# AUX_power_board_V3_4.net
KiCad netlist of a schematic drawn in EAGLE
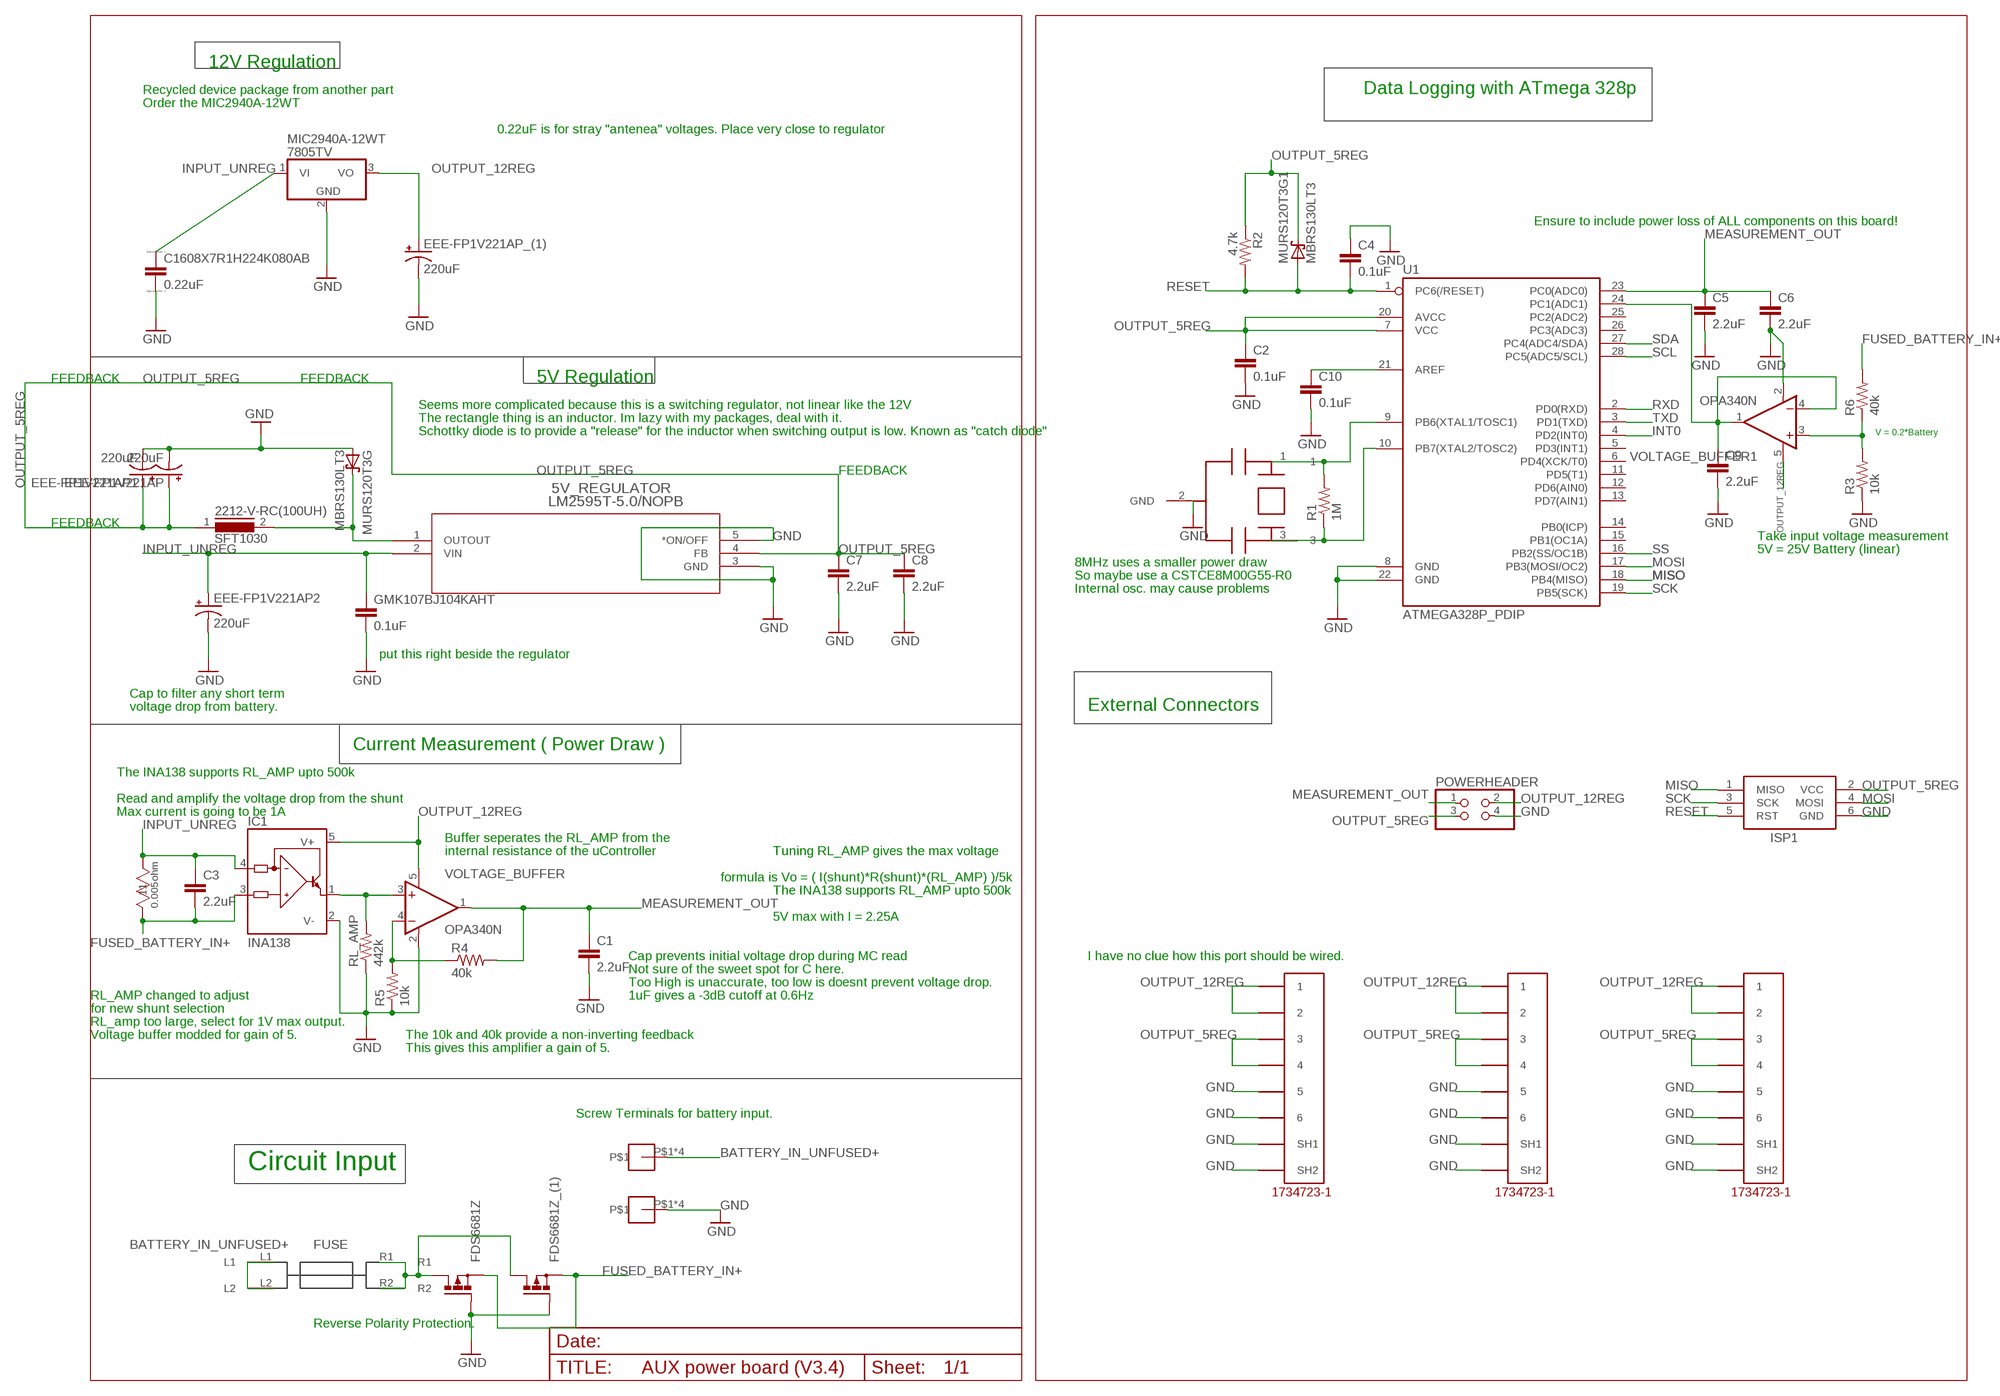
[diagram p0: schematic, sheet 1]

(export (version "E")
  (design (tool "Eeschema 10.0.6"))
  (components
    (comp (ref "5V_REGULATOR")
      (value "LM2595T-5.0/NOPB")
      (footprint "eagle-import:T05D")
      (fields
        (field (name "MANUFACTURER_PART_NUMBER") "LM2595T50")
        (field (name "COPYRIGHT") "Copyright C 2015 Accelerated Designs. All rights reserved")
      )
      (libsource (lib "eagle-import") (part "LM2595T-5.0/NOPB"))
    )
    (comp (ref "15FR005E")
      (value "15FR005E")
      (footprint "eagle-import:RES_15")
      (fields (field (name "COPYRIGHT") "Copyright C 2015 Accelerated Designs. All rights reserved"))
      (libsource (lib "eagle-import") (part "15FR005E"))
    )
    (comp (ref "2212-V-RC(100UH)")
      (value "SFT1030")
      (footprint "eagle-import:SFT1030")
      (libsource (lib "eagle-import") (part "SFT1030"))
    )
    (comp (ref "C1")
      (value "2.2uF")
      (footprint "eagle-import:C0603")
      (libsource (lib "eagle-import") (part "resistor_C-EUC0603"))
    )
    (comp (ref "C2")
      (value "0.1uF")
      (footprint "eagle-import:C0603")
      (libsource (lib "eagle-import") (part "resistor_C-EUC0603"))
    )
    (comp (ref "C3")
      (value "2.2uF")
      (footprint "eagle-import:C0603")
      (libsource (lib "eagle-import") (part "C-EUC0603"))
    )
    (comp (ref "C4")
      (value "0.1uF")
      (footprint "eagle-import:C0603")
      (libsource (lib "eagle-import") (part "C-EUC0603"))
    )
    (comp (ref "C5")
      (value "2.2uF")
      (footprint "eagle-import:C0603")
      (libsource (lib "eagle-import") (part "C-EUC0603"))
    )
    (comp (ref "C6")
      (value "2.2uF")
      (footprint "eagle-import:C0603")
      (libsource (lib "eagle-import") (part "C-EUC0603"))
    )
    (comp (ref "C7")
      (value "2.2uF")
      (footprint "eagle-import:C0603")
      (libsource (lib "eagle-import") (part "C-EUC0603"))
    )
    (comp (ref "C8")
      (value "2.2uF")
      (footprint "eagle-import:C0603")
      (libsource (lib "eagle-import") (part "C-EUC0603"))
    )
    (comp (ref "C9")
      (value "2.2uF")
      (footprint "eagle-import:C0603")
      (libsource (lib "eagle-import") (part "C-EUC0603"))
    )
    (comp (ref "C10")
      (value "0.1uF")
      (footprint "eagle-import:C0603")
      (libsource (lib "eagle-import") (part "resistor_C-EUC0603"))
    )
    (comp (ref "C1608X7R1H224K080AB")
      (value "0.22uF")
      (footprint "eagle-import:C0603")
      (libsource (lib "eagle-import") (part "CC0603"))
    )
    (comp (ref "CSTCE8M00G55-R0")
      (value "CSTCE16M0V53-R0")
      (footprint "eagle-import:RESONATOR")
      (libsource (lib "eagle-import") (part "CSTCE16M0V53-R0"))
    )
    (comp (ref "EEE-FP1V221AP")
      (value "220uF")
      (footprint "eagle-import:175TMP-0808")
      (libsource (lib "eagle-import") (part "CPOL-US175TMP-0808"))
    )
    (comp (ref "EEE-FP1V221AP1")
      (value "220uF")
      (footprint "eagle-import:175TMP-0808")
      (libsource (lib "eagle-import") (part "CPOL-US175TMP-0808"))
    )
    (comp (ref "EEE-FP1V221AP2")
      (value "220uF")
      (footprint "eagle-import:175TMP-0808")
      (libsource (lib "eagle-import") (part "CPOL-US175TMP-0808"))
    )
    (comp (ref "EEE-FP1V221AP_(1)")
      (value "220uF")
      (footprint "eagle-import:175TMP-0808")
      (libsource (lib "eagle-import") (part "CPOL-US175TMP-0808"))
    )
    (comp (ref "FDS6681Z")
      (value "P-MOSFET-SO8")
      (footprint "eagle-import:SO-08")
      (libsource (lib "eagle-import") (part "P-MOSFET-SO8"))
    )
    (comp (ref "FDS6681Z_(1)")
      (value "P-MOSFET-SO8")
      (footprint "eagle-import:SO-08")
      (libsource (lib "eagle-import") (part "P-MOSFET-SO8"))
    )
    (comp (ref "GMK107BJ104KAHT")
      (value "0.1uF")
      (footprint "eagle-import:C0603")
      (libsource (lib "eagle-import") (part "C-EUC0603"))
    )
    (comp (ref "IC1")
      (value "INA138")
      (footprint "eagle-import:SOT23-5")
      (fields (field (name "MF") "TEXAS INSTRUMENTS") (field (name "MPN") "INA138NA/250"))
      (libsource (lib "eagle-import") (part "INA138"))
    )
    (comp (ref "ISP1")
      (value "AVRISP-6")
      (footprint "eagle-import:AVRISP")
      (libsource (lib "eagle-import") (part "AVRISP-6"))
    )
    (comp (ref "MIC2940A-12WT")
      (value "7805TV")
      (footprint "eagle-import:TO220V")
      (libsource (lib "eagle-import") (part "78TV05"))
    )
    (comp (ref "MINIBLADE")
      (value "3568")
      (footprint "eagle-import:3568")
      (libsource (lib "eagle-import") (part "3568"))
    )
    (comp (ref "MURS120T3G")
      (value "MBRS130LT3")
      (footprint "eagle-import:SMB")
      (libsource (lib "eagle-import") (part "MBRS130LT3"))
    )
    (comp (ref "MURS120T3G1")
      (value "MBRS130LT3")
      (footprint "eagle-import:SMB")
      (libsource (lib "eagle-import") (part "MBRS130LT3"))
    )
    (comp (ref "POWERHEADER")
      (value "PINHD-2X2")
      (footprint "eagle-import:2X02")
      (libsource (lib "eagle-import") (part "PINHD-2X2"))
    )
    (comp (ref "R1")
      (value "1M")
      (footprint "eagle-import:R0603")
      (libsource (lib "eagle-import") (part "R-US_R0603"))
    )
    (comp (ref "R2")
      (value "4.7k")
      (footprint "eagle-import:R0603")
      (libsource (lib "eagle-import") (part "resistor_R-US_R0603"))
    )
    (comp (ref "R3")
      (value "10k")
      (footprint "eagle-import:R0603")
      (libsource (lib "eagle-import") (part "resistor_R-US_R0603"))
    )
    (comp (ref "R4")
      (value "40k")
      (footprint "eagle-import:R0603")
      (libsource (lib "eagle-import") (part "resistor_R-US_R0603"))
    )
    (comp (ref "R5")
      (value "10k")
      (footprint "eagle-import:R0603")
      (libsource (lib "eagle-import") (part "resistor_R-US_R0603"))
    )
    (comp (ref "R6")
      (value "40k")
      (footprint "eagle-import:R0603")
      (libsource (lib "eagle-import") (part "resistor_R-US_R0603"))
    )
    (comp (ref "RL_AMP")
      (value "442k")
      (footprint "eagle-import:R0603")
      (libsource (lib "eagle-import") (part "resistor_R-US_R0603"))
    )
    (comp (ref "U$3")
      (value "5555140-6")
      (footprint "eagle-import:1734723-1_RJ11")
      (libsource (lib "eagle-import") (part "5555140-6"))
    )
    (comp (ref "U$4")
      (value "5555140-6")
      (footprint "eagle-import:1734723-1_RJ11")
      (libsource (lib "eagle-import") (part "5555140-6"))
    )
    (comp (ref "U$5")
      (value "5555140-6")
      (footprint "eagle-import:1734723-1_RJ11")
      (libsource (lib "eagle-import") (part "5555140-6"))
    )
    (comp (ref "U$6")
      (value "SCREW-8191")
      (footprint "eagle-import:SCREW-8191")
      (libsource (lib "eagle-import") (part "SCREW-8191"))
    )
    (comp (ref "U$7")
      (value "SCREW-8191")
      (footprint "eagle-import:SCREW-8191")
      (libsource (lib "eagle-import") (part "SCREW-8191"))
    )
    (comp (ref "U1")
      (value "ATMEGA328P_PDIP")
      (footprint "eagle-import:DIL28-3")
      (libsource (lib "eagle-import") (part "ATMEGA328P_PDIP"))
    )
    (comp (ref "VOLTAGE_BUFFER")
      (value "OPA340N")
      (footprint "eagle-import:SOT23-5")
      (fields (field (name "MPN") "OPA340NA/3KG4"))
      (libsource (lib "eagle-import") (part "OPA340N"))
    )
    (comp (ref "VOLTAGE_BUFFER1")
      (value "OPA340N")
      (footprint "eagle-import:SOT23-5")
      (fields (field (name "MPN") "OPA340NA/3KG4"))
      (libsource (lib "eagle-import") (part "OPA340N"))
    )
  )
  (nets
    (net (code "1") (name "/BATTERY_IN_UNFUSED+") (class "Default")
      (node (ref "MINIBLADE") (pin "L1") (pinfunction "L1_L1") (pintype "bidirectional"))
      (node (ref "MINIBLADE") (pin "L2") (pinfunction "L2_L2") (pintype "bidirectional"))
      (node (ref "U$6") (pin "P$1") (pinfunction "P$1_P$1") (pintype "bidirectional"))
      (node (ref "U$6") (pin "P$2") (pinfunction "P$1_P$2") (pintype "bidirectional"))
      (node (ref "U$6") (pin "P$3") (pinfunction "P$1_P$3") (pintype "bidirectional"))
      (node (ref "U$6") (pin "P$4") (pinfunction "P$1_P$4") (pintype "bidirectional"))
    )
    (net (code "2") (name "/FUSED_BATTERY_IN+") (class "Default")
      (node (ref "15FR005E") (pin "1") (pinfunction "11_1") (pintype "passive"))
      (node (ref "C3") (pin "2") (pinfunction "2_2") (pintype "passive"))
      (node (ref "FDS6681Z") (pin "1") (pinfunction "S_1") (pintype "passive"))
      (node (ref "FDS6681Z") (pin "2") (pinfunction "S_2") (pintype "passive"))
      (node (ref "FDS6681Z") (pin "3") (pinfunction "S_3") (pintype "passive"))
      (node (ref "FDS6681Z_(1)") (pin "1") (pinfunction "S_1") (pintype "passive"))
      (node (ref "FDS6681Z_(1)") (pin "2") (pinfunction "S_2") (pintype "passive"))
      (node (ref "FDS6681Z_(1)") (pin "3") (pinfunction "S_3") (pintype "passive"))
      (node (ref "IC1") (pin "3") (pinfunction "IN+_3") (pintype "input"))
      (node (ref "R6") (pin "2") (pinfunction "2_2") (pintype "passive"))
    )
    (net (code "3") (name "/INPUT_UNREG") (class "Default")
      (node (ref "15FR005E") (pin "2") (pinfunction "22_2") (pintype "passive"))
      (node (ref "5V_REGULATOR") (pin "2") (pinfunction "VIN_2") (pintype "input"))
      (node (ref "C1608X7R1H224K080AB") (pin "1") (pinfunction "1_1") (pintype "passive"))
      (node (ref "C3") (pin "1") (pinfunction "1_1") (pintype "passive"))
      (node (ref "EEE-FP1V221AP2") (pin "+") (pinfunction "+_+") (pintype "passive"))
      (node (ref "GMK107BJ104KAHT") (pin "1") (pinfunction "1_1") (pintype "passive"))
      (node (ref "IC1") (pin "4") (pinfunction "IN-_4") (pintype "input"))
      (node (ref "MIC2940A-12WT") (pin "1") (pinfunction "VI_1") (pintype "input"))
    )
    (net (code "4") (name "/INT0") (class "Default")
      (node (ref "U1") (pin "4") (pinfunction "PD2(INT0)_4") (pintype "bidirectional"))
    )
    (net (code "5") (name "/MEASUREMENT_OUT") (class "Default")
      (node (ref "C1") (pin "1") (pinfunction "1_1") (pintype "passive"))
      (node (ref "C5") (pin "1") (pinfunction "1_1") (pintype "passive"))
      (node (ref "C6") (pin "1") (pinfunction "1_1") (pintype "passive"))
      (node (ref "POWERHEADER") (pin "1") (pinfunction "1_1") (pintype "passive"))
      (node (ref "R4") (pin "2") (pinfunction "2_2") (pintype "passive"))
      (node (ref "U1") (pin "23") (pinfunction "PC0(ADC0)_23") (pintype "bidirectional"))
      (node (ref "VOLTAGE_BUFFER") (pin "1") (pinfunction "OUT_1") (pintype "output"))
    )
    (net (code "6") (name "/MISO") (class "Default")
      (node (ref "ISP1") (pin "1") (pinfunction "MISO_1") (pintype "input"))
      (node (ref "U1") (pin "18") (pinfunction "PB4(MISO)_18") (pintype "bidirectional"))
    )
    (net (code "7") (name "/MOSI") (class "Default")
      (node (ref "ISP1") (pin "4") (pinfunction "MOSI_4") (pintype "output"))
      (node (ref "U1") (pin "17") (pinfunction "PB3(MOSI/OC2)_17") (pintype "bidirectional"))
    )
    (net (code "8") (name "/OUTPUT_5REG") (class "Default")
      (node (ref "2212-V-RC(100UH)") (pin "1") (pinfunction "1_1") (pintype "passive"))
      (node (ref "5V_REGULATOR") (pin "4") (pinfunction "FB_4") (pintype "passive"))
      (node (ref "C2") (pin "1") (pinfunction "1_1") (pintype "passive"))
      (node (ref "C7") (pin "1") (pinfunction "1_1") (pintype "passive"))
      (node (ref "C8") (pin "1") (pinfunction "1_1") (pintype "passive"))
      (node (ref "EEE-FP1V221AP") (pin "+") (pinfunction "+_+") (pintype "passive"))
      (node (ref "EEE-FP1V221AP1") (pin "+") (pinfunction "+_+") (pintype "passive"))
      (node (ref "ISP1") (pin "2") (pinfunction "VCC_2") (pintype "power_in"))
      (node (ref "MURS120T3G1") (pin "C") (pinfunction "C_C") (pintype "passive"))
      (node (ref "POWERHEADER") (pin "3") (pinfunction "3_3") (pintype "passive"))
      (node (ref "R2") (pin "1") (pinfunction "1_1") (pintype "passive"))
      (node (ref "U$3") (pin "3") (pinfunction "3_3") (pintype "bidirectional"))
      (node (ref "U$3") (pin "4") (pinfunction "4_4") (pintype "bidirectional"))
      (node (ref "U$4") (pin "3") (pinfunction "3_3") (pintype "bidirectional"))
      (node (ref "U$4") (pin "4") (pinfunction "4_4") (pintype "bidirectional"))
      (node (ref "U$5") (pin "3") (pinfunction "3_3") (pintype "bidirectional"))
      (node (ref "U$5") (pin "4") (pinfunction "4_4") (pintype "bidirectional"))
      (node (ref "U1") (pin "20") (pinfunction "AVCC_20") (pintype "bidirectional"))
      (node (ref "U1") (pin "7") (pinfunction "VCC_7") (pintype "bidirectional"))
    )
    (net (code "9") (name "/OUTPUT_12REG") (class "Default")
      (node (ref "EEE-FP1V221AP_(1)") (pin "+") (pinfunction "+_+") (pintype "passive"))
      (node (ref "IC1") (pin "5") (pinfunction "V+_5") (pintype "power_in"))
      (node (ref "MIC2940A-12WT") (pin "3") (pinfunction "VO_3") (pintype "passive"))
      (node (ref "POWERHEADER") (pin "2") (pinfunction "2_2") (pintype "passive"))
      (node (ref "U$3") (pin "1") (pinfunction "1_1") (pintype "bidirectional"))
      (node (ref "U$3") (pin "2") (pinfunction "2_2") (pintype "bidirectional"))
      (node (ref "U$4") (pin "1") (pinfunction "1_1") (pintype "bidirectional"))
      (node (ref "U$4") (pin "2") (pinfunction "2_2") (pintype "bidirectional"))
      (node (ref "U$5") (pin "1") (pinfunction "1_1") (pintype "bidirectional"))
      (node (ref "U$5") (pin "2") (pinfunction "2_2") (pintype "bidirectional"))
      (node (ref "VOLTAGE_BUFFER") (pin "5") (pinfunction "V+_5") (pintype "power_in"))
      (node (ref "VOLTAGE_BUFFER1") (pin "5") (pinfunction "V+_5") (pintype "power_in"))
    )
    (net (code "10") (name "/RESET") (class "Default")
      (node (ref "C4") (pin "2") (pinfunction "2_2") (pintype "passive"))
      (node (ref "ISP1") (pin "5") (pinfunction "RST_5") (pintype "output"))
      (node (ref "MURS120T3G1") (pin "A") (pinfunction "A_A") (pintype "passive"))
      (node (ref "R2") (pin "2") (pinfunction "2_2") (pintype "passive"))
      (node (ref "U1") (pin "1") (pinfunction "PC6(/RESET)_1") (pintype "bidirectional"))
    )
    (net (code "11") (name "/RXD") (class "Default")
      (node (ref "U1") (pin "2") (pinfunction "PD0(RXD)_2") (pintype "bidirectional"))
    )
    (net (code "12") (name "/SCK") (class "Default")
      (node (ref "ISP1") (pin "3") (pinfunction "SCK_3") (pintype "output"))
      (node (ref "U1") (pin "19") (pinfunction "PB5(SCK)_19") (pintype "bidirectional"))
    )
    (net (code "13") (name "/SCL") (class "Default")
      (node (ref "U1") (pin "28") (pinfunction "PC5(ADC5/SCL)_28") (pintype "bidirectional"))
    )
    (net (code "14") (name "/SDA") (class "Default")
      (node (ref "U1") (pin "27") (pinfunction "PC4(ADC4/SDA)_27") (pintype "bidirectional"))
    )
    (net (code "15") (name "/SS") (class "Default")
      (node (ref "U1") (pin "16") (pinfunction "PB2(SS/OC1B)_16") (pintype "bidirectional"))
    )
    (net (code "16") (name "/TXD") (class "Default")
      (node (ref "U1") (pin "3") (pinfunction "PD1(TXD)_3") (pintype "bidirectional"))
    )
    (net (code "17") (name "GND") (class "Default")
      (node (ref "5V_REGULATOR") (pin "3") (pinfunction "GND_3") (pintype "passive"))
      (node (ref "5V_REGULATOR") (pin "5") (pinfunction "*ON/OFF_5") (pintype "passive"))
      (node (ref "C1") (pin "2") (pinfunction "2_2") (pintype "passive"))
      (node (ref "C10") (pin "2") (pinfunction "2_2") (pintype "passive"))
      (node (ref "C1608X7R1H224K080AB") (pin "2") (pinfunction "2_2") (pintype "passive"))
      (node (ref "C2") (pin "2") (pinfunction "2_2") (pintype "passive"))
      (node (ref "C4") (pin "1") (pinfunction "1_1") (pintype "passive"))
      (node (ref "C5") (pin "2") (pinfunction "2_2") (pintype "passive"))
      (node (ref "C6") (pin "2") (pinfunction "2_2") (pintype "passive"))
      (node (ref "C7") (pin "2") (pinfunction "2_2") (pintype "passive"))
      (node (ref "C8") (pin "2") (pinfunction "2_2") (pintype "passive"))
      (node (ref "C9") (pin "2") (pinfunction "2_2") (pintype "passive"))
      (node (ref "CSTCE8M00G55-R0") (pin "2") (pinfunction "GND_2") (pintype "bidirectional"))
      (node (ref "EEE-FP1V221AP") (pin "-") (pinfunction "-_-") (pintype "passive"))
      (node (ref "EEE-FP1V221AP1") (pin "-") (pinfunction "-_-") (pintype "passive"))
      (node (ref "EEE-FP1V221AP2") (pin "-") (pinfunction "-_-") (pintype "passive"))
      (node (ref "EEE-FP1V221AP_(1)") (pin "-") (pinfunction "-_-") (pintype "passive"))
      (node (ref "FDS6681Z") (pin "4") (pinfunction "G_4") (pintype "passive"))
      (node (ref "FDS6681Z_(1)") (pin "4") (pinfunction "G_4") (pintype "passive"))
      (node (ref "GMK107BJ104KAHT") (pin "2") (pinfunction "2_2") (pintype "passive"))
      (node (ref "IC1") (pin "2") (pinfunction "V-_2") (pintype "power_in"))
      (node (ref "ISP1") (pin "6") (pinfunction "GND_6") (pintype "power_in"))
      (node (ref "MIC2940A-12WT") (pin "2") (pinfunction "GND_2") (pintype "passive"))
      (node (ref "MURS120T3G") (pin "A") (pinfunction "A_A") (pintype "passive"))
      (node (ref "POWERHEADER") (pin "4") (pinfunction "4_4") (pintype "passive"))
      (node (ref "R3") (pin "1") (pinfunction "1_1") (pintype "passive"))
      (node (ref "R5") (pin "1") (pinfunction "1_1") (pintype "passive"))
      (node (ref "RL_AMP") (pin "1") (pinfunction "1_1") (pintype "passive"))
      (node (ref "U$3") (pin "5") (pinfunction "5_5") (pintype "bidirectional"))
      (node (ref "U$3") (pin "6") (pinfunction "6_6") (pintype "bidirectional"))
      (node (ref "U$3") (pin "SH1") (pinfunction "SH1_SH1") (pintype "bidirectional"))
      (node (ref "U$3") (pin "SH2") (pinfunction "SH2_SH2") (pintype "bidirectional"))
      (node (ref "U$4") (pin "5") (pinfunction "5_5") (pintype "bidirectional"))
      (node (ref "U$4") (pin "6") (pinfunction "6_6") (pintype "bidirectional"))
      (node (ref "U$4") (pin "SH1") (pinfunction "SH1_SH1") (pintype "bidirectional"))
      (node (ref "U$4") (pin "SH2") (pinfunction "SH2_SH2") (pintype "bidirectional"))
      (node (ref "U$5") (pin "5") (pinfunction "5_5") (pintype "bidirectional"))
      (node (ref "U$5") (pin "6") (pinfunction "6_6") (pintype "bidirectional"))
      (node (ref "U$5") (pin "SH1") (pinfunction "SH1_SH1") (pintype "bidirectional"))
      (node (ref "U$5") (pin "SH2") (pinfunction "SH2_SH2") (pintype "bidirectional"))
      (node (ref "U$7") (pin "P$1") (pinfunction "P$1_P$1") (pintype "bidirectional"))
      (node (ref "U$7") (pin "P$2") (pinfunction "P$1_P$2") (pintype "bidirectional"))
      (node (ref "U$7") (pin "P$3") (pinfunction "P$1_P$3") (pintype "bidirectional"))
      (node (ref "U$7") (pin "P$4") (pinfunction "P$1_P$4") (pintype "bidirectional"))
      (node (ref "U1") (pin "22") (pinfunction "GND_22") (pintype "bidirectional"))
      (node (ref "U1") (pin "8") (pinfunction "GND_8") (pintype "bidirectional"))
      (node (ref "VOLTAGE_BUFFER") (pin "2") (pinfunction "V-_2") (pintype "power_in"))
      (node (ref "VOLTAGE_BUFFER1") (pin "2") (pinfunction "V-_2") (pintype "power_in"))
    )
    (net (code "18") (name "Net-(5V_REGULATOR-OUTOUT)") (class "Default")
      (node (ref "2212-V-RC(100UH)") (pin "2") (pinfunction "2_2") (pintype "passive"))
      (node (ref "5V_REGULATOR") (pin "1") (pinfunction "OUTOUT_1") (pintype "output"))
      (node (ref "MURS120T3G") (pin "C") (pinfunction "C_C") (pintype "passive"))
    )
    (net (code "19") (name "Net-(FDS6681Z-D-Pad5)") (class "Default")
      (node (ref "FDS6681Z") (pin "5") (pinfunction "D_5") (pintype "passive"))
      (node (ref "FDS6681Z") (pin "6") (pinfunction "D_6") (pintype "passive"))
      (node (ref "FDS6681Z") (pin "7") (pinfunction "D_7") (pintype "passive"))
      (node (ref "FDS6681Z") (pin "8") (pinfunction "D_8") (pintype "passive"))
      (node (ref "FDS6681Z_(1)") (pin "5") (pinfunction "D_5") (pintype "passive"))
      (node (ref "FDS6681Z_(1)") (pin "6") (pinfunction "D_6") (pintype "passive"))
      (node (ref "FDS6681Z_(1)") (pin "7") (pinfunction "D_7") (pintype "passive"))
      (node (ref "FDS6681Z_(1)") (pin "8") (pinfunction "D_8") (pintype "passive"))
      (node (ref "MINIBLADE") (pin "R1") (pinfunction "R1_R1") (pintype "bidirectional"))
      (node (ref "MINIBLADE") (pin "R2") (pinfunction "R2_R2") (pintype "bidirectional"))
    )
    (net (code "20") (name "Net-(IC1-OUT)") (class "Default")
      (node (ref "IC1") (pin "1") (pinfunction "OUT_1") (pintype "output"))
      (node (ref "RL_AMP") (pin "2") (pinfunction "2_2") (pintype "passive"))
      (node (ref "VOLTAGE_BUFFER") (pin "3") (pinfunction "+IN_3") (pintype "input"))
    )
    (net (code "21") (name "Net-(U1-AREF)") (class "Default")
      (node (ref "C10") (pin "1") (pinfunction "1_1") (pintype "passive"))
      (node (ref "U1") (pin "21") (pinfunction "AREF_21") (pintype "bidirectional"))
    )
    (net (code "22") (name "Net-(U1-PB6(XTAL1{slash}TOSC1))") (class "Default")
      (node (ref "CSTCE8M00G55-R0") (pin "1") (pinfunction "1_1") (pintype "bidirectional"))
      (node (ref "R1") (pin "2") (pinfunction "2_2") (pintype "passive"))
      (node (ref "U1") (pin "9") (pinfunction "PB6(XTAL1/TOSC1)_9") (pintype "bidirectional"))
    )
    (net (code "23") (name "Net-(U1-PB7(XTAL2{slash}TOSC2))") (class "Default")
      (node (ref "CSTCE8M00G55-R0") (pin "3") (pinfunction "3_3") (pintype "bidirectional"))
      (node (ref "R1") (pin "1") (pinfunction "1_1") (pintype "passive"))
      (node (ref "U1") (pin "10") (pinfunction "PB7(XTAL2/TOSC2)_10") (pintype "bidirectional"))
    )
    (net (code "24") (name "Net-(U1-PC1(ADC1))") (class "Default")
      (node (ref "C9") (pin "1") (pinfunction "1_1") (pintype "passive"))
      (node (ref "U1") (pin "24") (pinfunction "PC1(ADC1)_24") (pintype "bidirectional"))
      (node (ref "VOLTAGE_BUFFER1") (pin "1") (pinfunction "OUT_1") (pintype "output"))
      (node (ref "VOLTAGE_BUFFER1") (pin "4") (pinfunction "-IN_4") (pintype "input"))
    )
    (net (code "25") (name "Net-(VOLTAGE_BUFFER--IN)") (class "Default")
      (node (ref "R4") (pin "1") (pinfunction "1_1") (pintype "passive"))
      (node (ref "R5") (pin "2") (pinfunction "2_2") (pintype "passive"))
      (node (ref "VOLTAGE_BUFFER") (pin "4") (pinfunction "-IN_4") (pintype "input"))
    )
    (net (code "26") (name "Net-(VOLTAGE_BUFFER1-+IN)") (class "Default")
      (node (ref "R3") (pin "2") (pinfunction "2_2") (pintype "passive"))
      (node (ref "R6") (pin "1") (pinfunction "1_1") (pintype "passive"))
      (node (ref "VOLTAGE_BUFFER1") (pin "3") (pinfunction "+IN_3") (pintype "input"))
    )
    (net (code "27") (name "unconnected-(U1-PB0(ICP)-Pad14)") (class "Default")
      (node (ref "U1") (pin "14") (pinfunction "PB0(ICP)_14") (pintype "bidirectional"))
    )
    (net (code "28") (name "unconnected-(U1-PB1(OC1A)-Pad15)") (class "Default")
      (node (ref "U1") (pin "15") (pinfunction "PB1(OC1A)_15") (pintype "bidirectional"))
    )
    (net (code "29") (name "unconnected-(U1-PC2(ADC2)-Pad25)") (class "Default")
      (node (ref "U1") (pin "25") (pinfunction "PC2(ADC2)_25") (pintype "bidirectional"))
    )
    (net (code "30") (name "unconnected-(U1-PC3(ADC3)-Pad26)") (class "Default")
      (node (ref "U1") (pin "26") (pinfunction "PC3(ADC3)_26") (pintype "bidirectional"))
    )
    (net (code "31") (name "unconnected-(U1-PD3(INT1)-Pad5)") (class "Default")
      (node (ref "U1") (pin "5") (pinfunction "PD3(INT1)_5") (pintype "bidirectional"))
    )
    (net (code "32") (name "unconnected-(U1-PD4(XCK{slash}T0)-Pad6)") (class "Default")
      (node (ref "U1") (pin "6") (pinfunction "PD4(XCK/T0)_6") (pintype "bidirectional"))
    )
    (net (code "33") (name "unconnected-(U1-PD5(T1)-Pad11)") (class "Default")
      (node (ref "U1") (pin "11") (pinfunction "PD5(T1)_11") (pintype "bidirectional"))
    )
    (net (code "34") (name "unconnected-(U1-PD6(AIN0)-Pad12)") (class "Default")
      (node (ref "U1") (pin "12") (pinfunction "PD6(AIN0)_12") (pintype "bidirectional"))
    )
    (net (code "35") (name "unconnected-(U1-PD7(AIN1)-Pad13)") (class "Default")
      (node (ref "U1") (pin "13") (pinfunction "PD7(AIN1)_13") (pintype "bidirectional"))
    )
  )
)
